# line_sensor_ver1_0.net
KiCad netlist of a schematic drawn in EAGLE
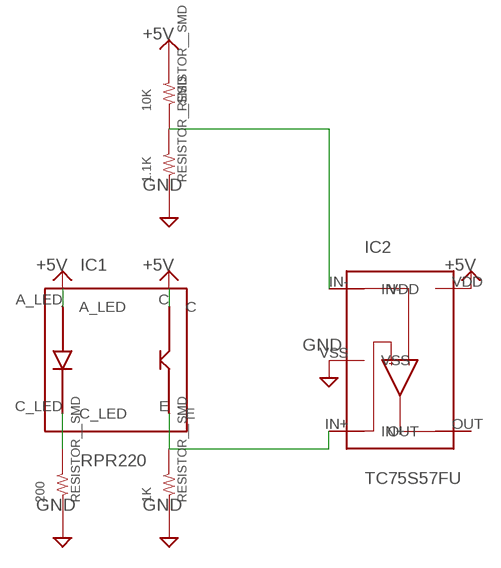
[diagram p0: schematic, sheet 1]

(export (version "E")
  (design (tool "Eeschema 10.0.6"))
  (components
    (comp (ref "1.1K")
      (value "RESISTOR__SMD")
      (footprint "eagle-import:1608")
      (libsource (lib "eagle-import") (part "RESISTOR__SMD"))
    )
    (comp (ref "1K")
      (value "RESISTOR__SMD")
      (footprint "eagle-import:1608")
      (libsource (lib "eagle-import") (part "RESISTOR__SMD"))
    )
    (comp (ref "10K")
      (value "RESISTOR__SMD")
      (footprint "eagle-import:1608")
      (libsource (lib "eagle-import") (part "RESISTOR__SMD"))
    )
    (comp (ref "200")
      (value "RESISTOR__SMD")
      (footprint "eagle-import:1608")
      (libsource (lib "eagle-import") (part "RESISTOR__SMD"))
    )
    (comp (ref "IC1")
      (value "RPR220")
      (footprint "eagle-import:RPR220")
      (libsource (lib "eagle-import") (part "RPR220"))
    )
    (comp (ref "IC2")
      (value "TC75S57FU")
      (footprint "eagle-import:SSOP5-P-0.65A")
      (libsource (lib "eagle-import") (part "TC75S57FU"))
    )
  )
  (nets
    (net (code "1") (name "+5V") (class "Default")
      (node (ref "10K") (pin "2") (pinfunction "P$2_2") (pintype "passive"))
      (node (ref "IC1") (pin "A_LED") (pinfunction "A_LED_A_LED") (pintype "bidirectional"))
      (node (ref "IC1") (pin "C") (pinfunction "C_C") (pintype "bidirectional"))
      (node (ref "IC2") (pin "VDD") (pinfunction "VDD_VDD") (pintype "bidirectional"))
    )
    (net (code "2") (name "GND") (class "Default")
      (node (ref "1.1K") (pin "1") (pinfunction "P$1_1") (pintype "passive"))
      (node (ref "1K") (pin "1") (pinfunction "P$1_1") (pintype "passive"))
      (node (ref "200") (pin "1") (pinfunction "P$1_1") (pintype "passive"))
      (node (ref "IC2") (pin "VSS") (pinfunction "VSS_VSS") (pintype "bidirectional"))
    )
    (net (code "3") (name "Net-(1.1K-P$2)") (class "Default")
      (node (ref "1.1K") (pin "2") (pinfunction "P$2_2") (pintype "passive"))
      (node (ref "10K") (pin "1") (pinfunction "P$1_1") (pintype "passive"))
      (node (ref "IC2") (pin "IN-") (pinfunction "IN-_IN-") (pintype "bidirectional"))
    )
    (net (code "4") (name "Net-(1K-P$2)") (class "Default")
      (node (ref "1K") (pin "2") (pinfunction "P$2_2") (pintype "passive"))
      (node (ref "IC1") (pin "E") (pinfunction "E_E") (pintype "bidirectional"))
      (node (ref "IC2") (pin "IN+") (pinfunction "IN+_IN+") (pintype "bidirectional"))
    )
    (net (code "5") (name "Net-(200-P$2)") (class "Default")
      (node (ref "200") (pin "2") (pinfunction "P$2_2") (pintype "passive"))
      (node (ref "IC1") (pin "C_LED") (pinfunction "C_LED_C_LED") (pintype "bidirectional"))
    )
    (net (code "6") (name "unconnected-(IC2-PadOUT)") (class "Default")
      (node (ref "IC2") (pin "OUT") (pinfunction "OUT_OUT") (pintype "bidirectional"))
    )
  )
)
